# Sheet4.net
KiCad netlist of a schematic drawn in Altium Designer
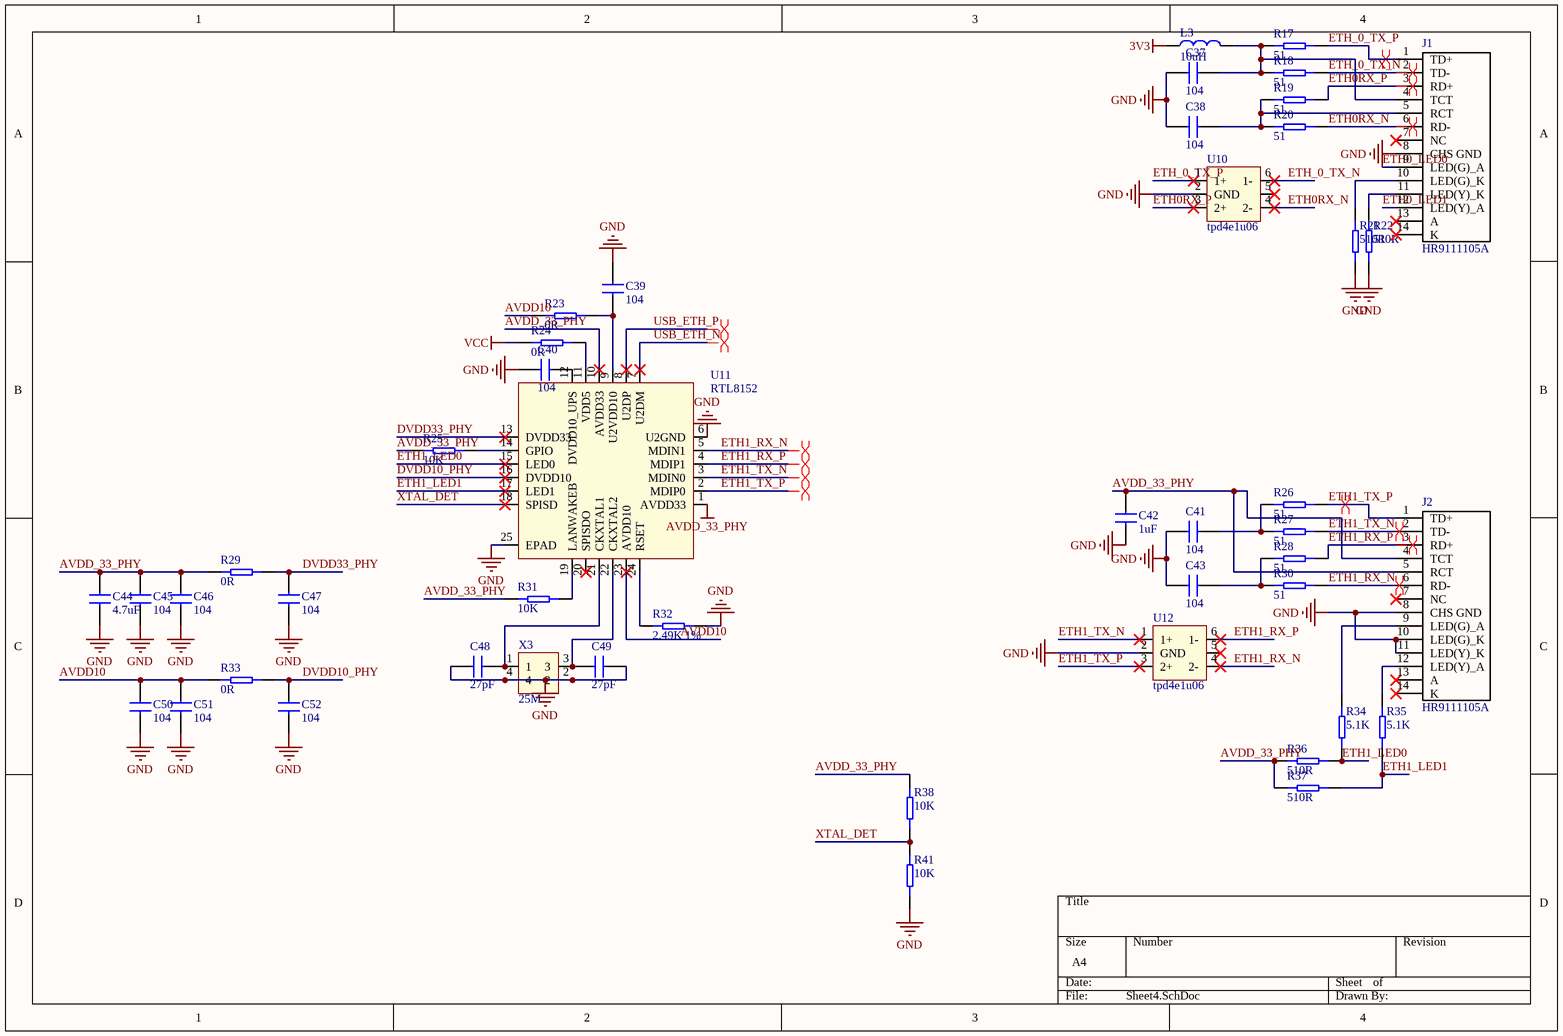
[diagram p0: Sheet4.SchDoc]

(export (version "E")
  (design (tool "Eeschema 10.0.6"))
  (components
    (comp (ref "C37")
      (value "104")
      (footprint "0402C")
      (description "SMD-CAP")
      (libsource (lib "Zero") (part "CAP"))
    )
    (comp (ref "C38")
      (value "104")
      (footprint "0402C")
      (description "SMD-CAP")
      (libsource (lib "Zero") (part "CAP"))
    )
    (comp (ref "C39")
      (value "104")
      (footprint "0402C")
      (description "SMD-CAP")
      (libsource (lib "Zero") (part "CAP"))
    )
    (comp (ref "C40")
      (value "104")
      (footprint "0402C")
      (description "SMD-CAP")
      (libsource (lib "Zero") (part "CAP"))
    )
    (comp (ref "C41")
      (value "104")
      (footprint "0402C")
      (description "SMD-CAP")
      (libsource (lib "Zero") (part "CAP"))
    )
    (comp (ref "C42")
      (value "1uF")
      (footprint "0603C")
      (description "SMD-CAP")
      (libsource (lib "Zero") (part "CAP"))
    )
    (comp (ref "C43")
      (value "104")
      (footprint "0402C")
      (description "SMD-CAP")
      (libsource (lib "Zero") (part "CAP"))
    )
    (comp (ref "C44")
      (value "4.7uF")
      (footprint "0603C")
      (description "SMD-CAP")
      (libsource (lib "Zero") (part "CAP"))
    )
    (comp (ref "C45")
      (value "104")
      (footprint "0402C")
      (description "SMD-CAP")
      (libsource (lib "Zero") (part "CAP"))
    )
    (comp (ref "C46")
      (value "104")
      (footprint "0402C")
      (description "SMD-CAP")
      (libsource (lib "Zero") (part "CAP"))
    )
    (comp (ref "C47")
      (value "104")
      (footprint "0402C")
      (description "SMD-CAP")
      (libsource (lib "Zero") (part "CAP"))
    )
    (comp (ref "C48")
      (value "27pF")
      (footprint "0402C")
      (description "SMD-CAP")
      (libsource (lib "Zero") (part "CAP"))
    )
    (comp (ref "C49")
      (value "27pF")
      (footprint "0402C")
      (description "SMD-CAP")
      (libsource (lib "Zero") (part "CAP"))
    )
    (comp (ref "C50")
      (value "104")
      (footprint "0402C")
      (description "SMD-CAP")
      (libsource (lib "Zero") (part "CAP"))
    )
    (comp (ref "C51")
      (value "104")
      (footprint "0402C")
      (description "SMD-CAP")
      (libsource (lib "Zero") (part "CAP"))
    )
    (comp (ref "C52")
      (value "104")
      (footprint "0402C")
      (description "SMD-CAP")
      (libsource (lib "Zero") (part "CAP"))
    )
    (comp (ref "J1")
      (value "HR9111105A")
      (footprint "RJ45-HR9111105A")
      (libsource (lib "插座") (part "RJ45-HR9111105A"))
    )
    (comp (ref "J2")
      (value "HR9111105A")
      (footprint "RJ45-HR9111105A")
      (libsource (lib "插座") (part "RJ45-HR9111105A"))
    )
    (comp (ref "L3")
      (value "10uH")
      (footprint "0805R")
      (description "电感")
      (libsource (lib "Zero") (part "L1"))
    )
    (comp (ref "R17") (value "51") (footprint "0402R") (libsource (lib "Zero") (part "R")))
    (comp (ref "R18") (value "51") (footprint "0402R") (libsource (lib "Zero") (part "R")))
    (comp (ref "R19") (value "51") (footprint "0402R") (libsource (lib "Zero") (part "R")))
    (comp (ref "R20") (value "51") (footprint "0402R") (libsource (lib "Zero") (part "R")))
    (comp (ref "R21") (value "510R") (footprint "0402R") (libsource (lib "Zero") (part "R")))
    (comp (ref "R22") (value "510R") (footprint "0402R") (libsource (lib "Zero") (part "R")))
    (comp (ref "R23") (value "0R") (footprint "0402R") (libsource (lib "Zero") (part "R")))
    (comp (ref "R24") (value "0R") (footprint "0805R") (libsource (lib "Zero") (part "R")))
    (comp (ref "R25") (value "10K") (footprint "0402R") (libsource (lib "Zero") (part "R")))
    (comp (ref "R26") (value "51") (footprint "0402R") (libsource (lib "Zero") (part "R")))
    (comp (ref "R27") (value "51") (footprint "0402R") (libsource (lib "Zero") (part "R")))
    (comp (ref "R28") (value "51") (footprint "0402R") (libsource (lib "Zero") (part "R")))
    (comp (ref "R29") (value "0R") (footprint "0402R") (libsource (lib "Zero") (part "R")))
    (comp (ref "R30") (value "51") (footprint "0402R") (libsource (lib "Zero") (part "R")))
    (comp (ref "R31") (value "10K") (footprint "0402R") (libsource (lib "Zero") (part "R")))
    (comp (ref "R32") (value "2.49K 1%") (footprint "0402R") (libsource (lib "Zero") (part "R")))
    (comp (ref "R33") (value "0R") (footprint "0402R") (libsource (lib "Zero") (part "R")))
    (comp (ref "R34") (value "5.1K") (footprint "0402R") (libsource (lib "Zero") (part "R")))
    (comp (ref "R35") (value "5.1K") (footprint "0402R") (libsource (lib "Zero") (part "R")))
    (comp (ref "R36") (value "510R") (footprint "0402R") (libsource (lib "Zero") (part "R")))
    (comp (ref "R37") (value "510R") (footprint "0402R") (libsource (lib "Zero") (part "R")))
    (comp (ref "R38") (value "10K") (footprint "0402R") (libsource (lib "") (part "R_1")))
    (comp (ref "R41") (value "10K") (footprint "0402R") (libsource (lib "") (part "R_1")))
    (comp (ref "U10")
      (value "tpd4e1u06")
      (footprint "tpd4e1u06")
      (libsource (lib "20180125H1") (part "tpd4e1u06"))
    )
    (comp (ref "U11")
      (value "RTL8152")
      (footprint "RTL8152B")
      (libsource (lib "20180125H1") (part "RTL8152"))
    )
    (comp (ref "U12")
      (value "tpd4e1u06")
      (footprint "tpd4e1u06")
      (libsource (lib "20180125H1") (part "tpd4e1u06"))
    )
    (comp (ref "X3")
      (value "25M")
      (footprint "LC-SMD-3225_4P")
      (libsource (lib "20180125H1") (part "XTAL-4pin"))
    )
  )
  (nets
    (net (code "1") (name "/AVDD10") (class "Default")
      (node (ref "C50") (pin "1") (pinfunction "1_1") (pintype "passive"))
      (node (ref "C51") (pin "1") (pinfunction "1_1") (pintype "passive"))
      (node (ref "R23") (pin "1") (pinfunction "1_1") (pintype "passive"))
      (node (ref "R33") (pin "1") (pinfunction "1_1") (pintype "passive"))
      (node (ref "U11") (pin "23") (pinfunction "AVDD10_23") (pintype "passive"))
    )
    (net (code "2") (name "/DVDD10_PHY") (class "Default")
      (node (ref "C52") (pin "1") (pinfunction "1_1") (pintype "passive"))
      (node (ref "R33") (pin "2") (pinfunction "2_2") (pintype "passive"))
      (node (ref "U11") (pin "16") (pinfunction "DVDD10_16") (pintype "passive"))
    )
    (net (code "3") (name "/DVDD33_PHY") (class "Default")
      (node (ref "C47") (pin "1") (pinfunction "1_1") (pintype "passive"))
      (node (ref "R29") (pin "2") (pinfunction "2_2") (pintype "passive"))
      (node (ref "U11") (pin "13") (pinfunction "DVDD33_13") (pintype "passive"))
    )
    (net (code "4") (name "/ETH0RX_N") (class "Default")
      (node (ref "J1") (pin "6") (pinfunction "RD-_6") (pintype "passive"))
      (node (ref "R20") (pin "2") (pinfunction "2_2") (pintype "passive"))
      (node (ref "U10") (pin "4") (pinfunction "2-_4") (pintype "passive"))
    )
    (net (code "5") (name "/ETH0RX_P") (class "Default")
      (node (ref "J1") (pin "3") (pinfunction "RD+_3") (pintype "passive"))
      (node (ref "R19") (pin "2") (pinfunction "2_2") (pintype "passive"))
      (node (ref "U10") (pin "3") (pinfunction "2+_3") (pintype "passive"))
    )
    (net (code "6") (name "/ETH0_LED0") (class "Default")
      (node (ref "J1") (pin "9") (pinfunction "LED(G)_A_9") (pintype "passive"))
    )
    (net (code "7") (name "/ETH0_LED1") (class "Default")
      (node (ref "J1") (pin "12") (pinfunction "LED(Y)_A_12") (pintype "passive"))
    )
    (net (code "8") (name "/ETH1_LED0") (class "Default")
      (node (ref "R34") (pin "2") (pinfunction "2_2") (pintype "passive"))
      (node (ref "R36") (pin "1") (pinfunction "1_1") (pintype "passive"))
      (node (ref "U11") (pin "15") (pinfunction "LED0_15") (pintype "passive"))
    )
    (net (code "9") (name "/ETH1_LED1") (class "Default")
      (node (ref "R35") (pin "2") (pinfunction "2_2") (pintype "passive"))
      (node (ref "R37") (pin "1") (pinfunction "1_1") (pintype "passive"))
      (node (ref "U11") (pin "17") (pinfunction "LED1_17") (pintype "passive"))
    )
    (net (code "10") (name "/ETH1_RX_N") (class "Default")
      (node (ref "J2") (pin "6") (pinfunction "RD-_6") (pintype "passive"))
      (node (ref "R30") (pin "2") (pinfunction "2_2") (pintype "passive"))
      (node (ref "U11") (pin "5") (pinfunction "MDIN1_5") (pintype "passive"))
      (node (ref "U12") (pin "4") (pinfunction "2-_4") (pintype "passive"))
    )
    (net (code "11") (name "/ETH1_RX_P") (class "Default")
      (node (ref "J2") (pin "3") (pinfunction "RD+_3") (pintype "passive"))
      (node (ref "R28") (pin "2") (pinfunction "2_2") (pintype "passive"))
      (node (ref "U11") (pin "4") (pinfunction "MDIP1_4") (pintype "passive"))
      (node (ref "U12") (pin "6") (pinfunction "1-_6") (pintype "passive"))
    )
    (net (code "12") (name "/ETH1_TX_N") (class "Default")
      (node (ref "J2") (pin "2") (pinfunction "TD-_2") (pintype "passive"))
      (node (ref "R27") (pin "2") (pinfunction "2_2") (pintype "passive"))
      (node (ref "U11") (pin "3") (pinfunction "MDIN0_3") (pintype "passive"))
      (node (ref "U12") (pin "1") (pinfunction "1+_1") (pintype "passive"))
    )
    (net (code "13") (name "/ETH1_TX_P") (class "Default")
      (node (ref "J2") (pin "1") (pinfunction "TD+_1") (pintype "passive"))
      (node (ref "R26") (pin "2") (pinfunction "2_2") (pintype "passive"))
      (node (ref "U11") (pin "2") (pinfunction "MDIP0_2") (pintype "passive"))
      (node (ref "U12") (pin "3") (pinfunction "2+_3") (pintype "passive"))
    )
    (net (code "14") (name "/ETH_0_TX_N") (class "Default")
      (node (ref "J1") (pin "2") (pinfunction "TD-_2") (pintype "passive"))
      (node (ref "R18") (pin "2") (pinfunction "2_2") (pintype "passive"))
      (node (ref "U10") (pin "6") (pinfunction "1-_6") (pintype "passive"))
    )
    (net (code "15") (name "/ETH_0_TX_P") (class "Default")
      (node (ref "J1") (pin "1") (pinfunction "TD+_1") (pintype "passive"))
      (node (ref "R17") (pin "2") (pinfunction "2_2") (pintype "passive"))
      (node (ref "U10") (pin "1") (pinfunction "1+_1") (pintype "passive"))
    )
    (net (code "16") (name "/USB_ETH_N") (class "Default")
      (node (ref "U11") (pin "7") (pinfunction "U2DM_7") (pintype "passive+no_connect"))
    )
    (net (code "17") (name "/USB_ETH_P") (class "Default")
      (node (ref "U11") (pin "8") (pinfunction "U2DP_8") (pintype "passive+no_connect"))
    )
    (net (code "18") (name "/XTAL_DET") (class "Default")
      (node (ref "R38") (pin "1") (pinfunction "1_1") (pintype "passive"))
      (node (ref "R41") (pin "2") (pinfunction "2_2") (pintype "passive"))
      (node (ref "U11") (pin "18") (pinfunction "SPISD_18") (pintype "passive"))
    )
    (net (code "19") (name "3V3") (class "Default")
      (node (ref "L3") (pin "2") (pinfunction "2_2") (pintype "passive"))
    )
    (net (code "20") (name "AVDD_33_PHY") (class "Default")
      (node (ref "C42") (pin "1") (pinfunction "1_1") (pintype "passive"))
      (node (ref "C44") (pin "1") (pinfunction "1_1") (pintype "passive"))
      (node (ref "C45") (pin "1") (pinfunction "1_1") (pintype "passive"))
      (node (ref "C46") (pin "1") (pinfunction "1_1") (pintype "passive"))
      (node (ref "J2") (pin "4") (pinfunction "TCT_4") (pintype "passive"))
      (node (ref "J2") (pin "5") (pinfunction "RCT_5") (pintype "passive"))
      (node (ref "R25") (pin "1") (pinfunction "1_1") (pintype "passive"))
      (node (ref "R29") (pin "1") (pinfunction "1_1") (pintype "passive"))
      (node (ref "R31") (pin "1") (pinfunction "1_1") (pintype "passive"))
      (node (ref "R36") (pin "2") (pinfunction "2_2") (pintype "passive"))
      (node (ref "R37") (pin "2") (pinfunction "2_2") (pintype "passive"))
      (node (ref "R38") (pin "2") (pinfunction "2_2") (pintype "passive"))
      (node (ref "U11") (pin "1") (pinfunction "AVDD33_1") (pintype "passive"))
      (node (ref "U11") (pin "10") (pinfunction "AVDD33_10") (pintype "passive"))
    )
    (net (code "21") (name "GND") (class "Default")
      (node (ref "C37") (pin "1") (pinfunction "1_1") (pintype "passive"))
      (node (ref "C38") (pin "1") (pinfunction "1_1") (pintype "passive"))
      (node (ref "C39") (pin "2") (pinfunction "2_2") (pintype "passive"))
      (node (ref "C40") (pin "1") (pinfunction "1_1") (pintype "passive"))
      (node (ref "C41") (pin "1") (pinfunction "1_1") (pintype "passive"))
      (node (ref "C42") (pin "2") (pinfunction "2_2") (pintype "passive"))
      (node (ref "C43") (pin "1") (pinfunction "1_1") (pintype "passive"))
      (node (ref "C44") (pin "2") (pinfunction "2_2") (pintype "passive"))
      (node (ref "C45") (pin "2") (pinfunction "2_2") (pintype "passive"))
      (node (ref "C46") (pin "2") (pinfunction "2_2") (pintype "passive"))
      (node (ref "C47") (pin "2") (pinfunction "2_2") (pintype "passive"))
      (node (ref "C48") (pin "1") (pinfunction "1_1") (pintype "passive"))
      (node (ref "C49") (pin "2") (pinfunction "2_2") (pintype "passive"))
      (node (ref "C50") (pin "2") (pinfunction "2_2") (pintype "passive"))
      (node (ref "C51") (pin "2") (pinfunction "2_2") (pintype "passive"))
      (node (ref "C52") (pin "2") (pinfunction "2_2") (pintype "passive"))
      (node (ref "J1") (pin "8") (pinfunction "CHS_GND_8") (pintype "passive"))
      (node (ref "J2") (pin "10") (pinfunction "LED(G)_K_10") (pintype "passive"))
      (node (ref "J2") (pin "11") (pinfunction "LED(Y)_K_11") (pintype "passive"))
      (node (ref "J2") (pin "8") (pinfunction "CHS_GND_8") (pintype "passive"))
      (node (ref "R21") (pin "1") (pinfunction "1_1") (pintype "passive"))
      (node (ref "R22") (pin "1") (pinfunction "1_1") (pintype "passive"))
      (node (ref "R32") (pin "1") (pinfunction "1_1") (pintype "passive"))
      (node (ref "R41") (pin "1") (pinfunction "1_1") (pintype "passive"))
      (node (ref "U10") (pin "2") (pinfunction "GND_2") (pintype "passive"))
      (node (ref "U11") (pin "25") (pinfunction "EPAD_25") (pintype "passive"))
      (node (ref "U11") (pin "6") (pinfunction "U2GND_6") (pintype "passive"))
      (node (ref "U12") (pin "2") (pinfunction "GND_2") (pintype "passive"))
      (node (ref "X3") (pin "2") (pinfunction "2_2") (pintype "passive"))
      (node (ref "X3") (pin "4") (pinfunction "4_4") (pintype "passive"))
    )
    (net (code "22") (name "Net-(C41-Pad2)") (class "Default")
      (node (ref "C41") (pin "2") (pinfunction "2_2") (pintype "passive"))
      (node (ref "R26") (pin "1") (pinfunction "1_1") (pintype "passive"))
      (node (ref "R27") (pin "1") (pinfunction "1_1") (pintype "passive"))
    )
    (net (code "23") (name "Net-(C43-Pad2)") (class "Default")
      (node (ref "C43") (pin "2") (pinfunction "2_2") (pintype "passive"))
      (node (ref "R28") (pin "1") (pinfunction "1_1") (pintype "passive"))
      (node (ref "R30") (pin "1") (pinfunction "1_1") (pintype "passive"))
    )
    (net (code "24") (name "Net-(J1-LED(G)_K)") (class "Default")
      (node (ref "J1") (pin "10") (pinfunction "LED(G)_K_10") (pintype "passive"))
      (node (ref "R21") (pin "2") (pinfunction "2_2") (pintype "passive"))
    )
    (net (code "25") (name "Net-(J1-LED(Y)_K)") (class "Default")
      (node (ref "J1") (pin "11") (pinfunction "LED(Y)_K_11") (pintype "passive"))
      (node (ref "R22") (pin "2") (pinfunction "2_2") (pintype "passive"))
    )
    (net (code "26") (name "Net-(J1-RCT)") (class "Default")
      (node (ref "C38") (pin "2") (pinfunction "2_2") (pintype "passive"))
      (node (ref "J1") (pin "5") (pinfunction "RCT_5") (pintype "passive"))
      (node (ref "R19") (pin "1") (pinfunction "1_1") (pintype "passive"))
      (node (ref "R20") (pin "1") (pinfunction "1_1") (pintype "passive"))
    )
    (net (code "27") (name "Net-(J1-TCT)") (class "Default")
      (node (ref "C37") (pin "2") (pinfunction "2_2") (pintype "passive"))
      (node (ref "J1") (pin "4") (pinfunction "TCT_4") (pintype "passive"))
      (node (ref "L3") (pin "1") (pinfunction "1_1") (pintype "passive"))
      (node (ref "R17") (pin "1") (pinfunction "1_1") (pintype "passive"))
      (node (ref "R18") (pin "1") (pinfunction "1_1") (pintype "passive"))
    )
    (net (code "28") (name "Net-(J2-LED(G)_A)") (class "Default")
      (node (ref "J2") (pin "9") (pinfunction "LED(G)_A_9") (pintype "passive"))
      (node (ref "R34") (pin "1") (pinfunction "1_1") (pintype "passive"))
    )
    (net (code "29") (name "Net-(J2-LED(Y)_A)") (class "Default")
      (node (ref "J2") (pin "12") (pinfunction "LED(Y)_A_12") (pintype "passive"))
      (node (ref "R35") (pin "1") (pinfunction "1_1") (pintype "passive"))
    )
    (net (code "30") (name "Net-(U11-CKXTAL1)") (class "Default")
      (node (ref "C48") (pin "2") (pinfunction "2_2") (pintype "passive"))
      (node (ref "U11") (pin "21") (pinfunction "CKXTAL1_21") (pintype "passive"))
      (node (ref "X3") (pin "1") (pinfunction "1_1") (pintype "passive"))
    )
    (net (code "31") (name "Net-(U11-CKXTAL2)") (class "Default")
      (node (ref "C49") (pin "1") (pinfunction "1_1") (pintype "passive"))
      (node (ref "U11") (pin "22") (pinfunction "CKXTAL2_22") (pintype "passive"))
      (node (ref "X3") (pin "3") (pinfunction "3_3") (pintype "passive"))
    )
    (net (code "32") (name "Net-(U11-DVDD10_UPS)") (class "Default")
      (node (ref "C40") (pin "2") (pinfunction "2_2") (pintype "passive"))
      (node (ref "U11") (pin "12") (pinfunction "DVDD10_UPS_12") (pintype "passive"))
    )
    (net (code "33") (name "Net-(U11-GPIO)") (class "Default")
      (node (ref "R25") (pin "2") (pinfunction "2_2") (pintype "passive"))
      (node (ref "U11") (pin "14") (pinfunction "GPIO_14") (pintype "passive"))
    )
    (net (code "34") (name "Net-(U11-LANWAKEB)") (class "Default")
      (node (ref "R31") (pin "2") (pinfunction "2_2") (pintype "passive"))
      (node (ref "U11") (pin "19") (pinfunction "LANWAKEB_19") (pintype "passive"))
    )
    (net (code "35") (name "Net-(U11-RSET)") (class "Default")
      (node (ref "R32") (pin "2") (pinfunction "2_2") (pintype "passive"))
      (node (ref "U11") (pin "24") (pinfunction "RSET_24") (pintype "passive"))
    )
    (net (code "36") (name "Net-(U11-U2VDD10)") (class "Default")
      (node (ref "C39") (pin "1") (pinfunction "1_1") (pintype "passive"))
      (node (ref "R23") (pin "2") (pinfunction "2_2") (pintype "passive"))
      (node (ref "U11") (pin "9") (pinfunction "U2VDD10_9") (pintype "passive"))
    )
    (net (code "37") (name "Net-(U11-VDD5)") (class "Default")
      (node (ref "R24") (pin "2") (pinfunction "2_2") (pintype "passive"))
      (node (ref "U11") (pin "11") (pinfunction "VDD5_11") (pintype "passive"))
    )
    (net (code "38") (name "VCC") (class "Default")
      (node (ref "R24") (pin "1") (pinfunction "1_1") (pintype "passive"))
    )
    (net (code "39") (name "unconnected-(J1-A-Pad13)") (class "Default")
      (node (ref "J1") (pin "13") (pinfunction "A_13") (pintype "passive+no_connect"))
    )
    (net (code "40") (name "unconnected-(J1-K-Pad14)") (class "Default")
      (node (ref "J1") (pin "14") (pinfunction "K_14") (pintype "passive+no_connect"))
    )
    (net (code "41") (name "unconnected-(J1-NC-Pad7)") (class "Default")
      (node (ref "J1") (pin "7") (pinfunction "NC_7") (pintype "passive+no_connect"))
    )
    (net (code "42") (name "unconnected-(J2-A-Pad13)") (class "Default")
      (node (ref "J2") (pin "13") (pinfunction "A_13") (pintype "passive+no_connect"))
    )
    (net (code "43") (name "unconnected-(J2-K-Pad14)") (class "Default")
      (node (ref "J2") (pin "14") (pinfunction "K_14") (pintype "passive+no_connect"))
    )
    (net (code "44") (name "unconnected-(J2-NC-Pad7)") (class "Default")
      (node (ref "J2") (pin "7") (pinfunction "NC_7") (pintype "passive+no_connect"))
    )
    (net (code "45") (name "unconnected-(U10-Pad5)") (class "Default")
      (node (ref "U10") (pin "5") (pintype "passive+no_connect"))
    )
    (net (code "46") (name "unconnected-(U11-SPISDO-Pad20)") (class "Default")
      (node (ref "U11") (pin "20") (pinfunction "SPISDO_20") (pintype "passive+no_connect"))
    )
    (net (code "47") (name "unconnected-(U12-Pad5)") (class "Default")
      (node (ref "U12") (pin "5") (pintype "passive+no_connect"))
    )
  )
)
